# Comm.net
KiCad netlist of a schematic drawn in Altium Designer
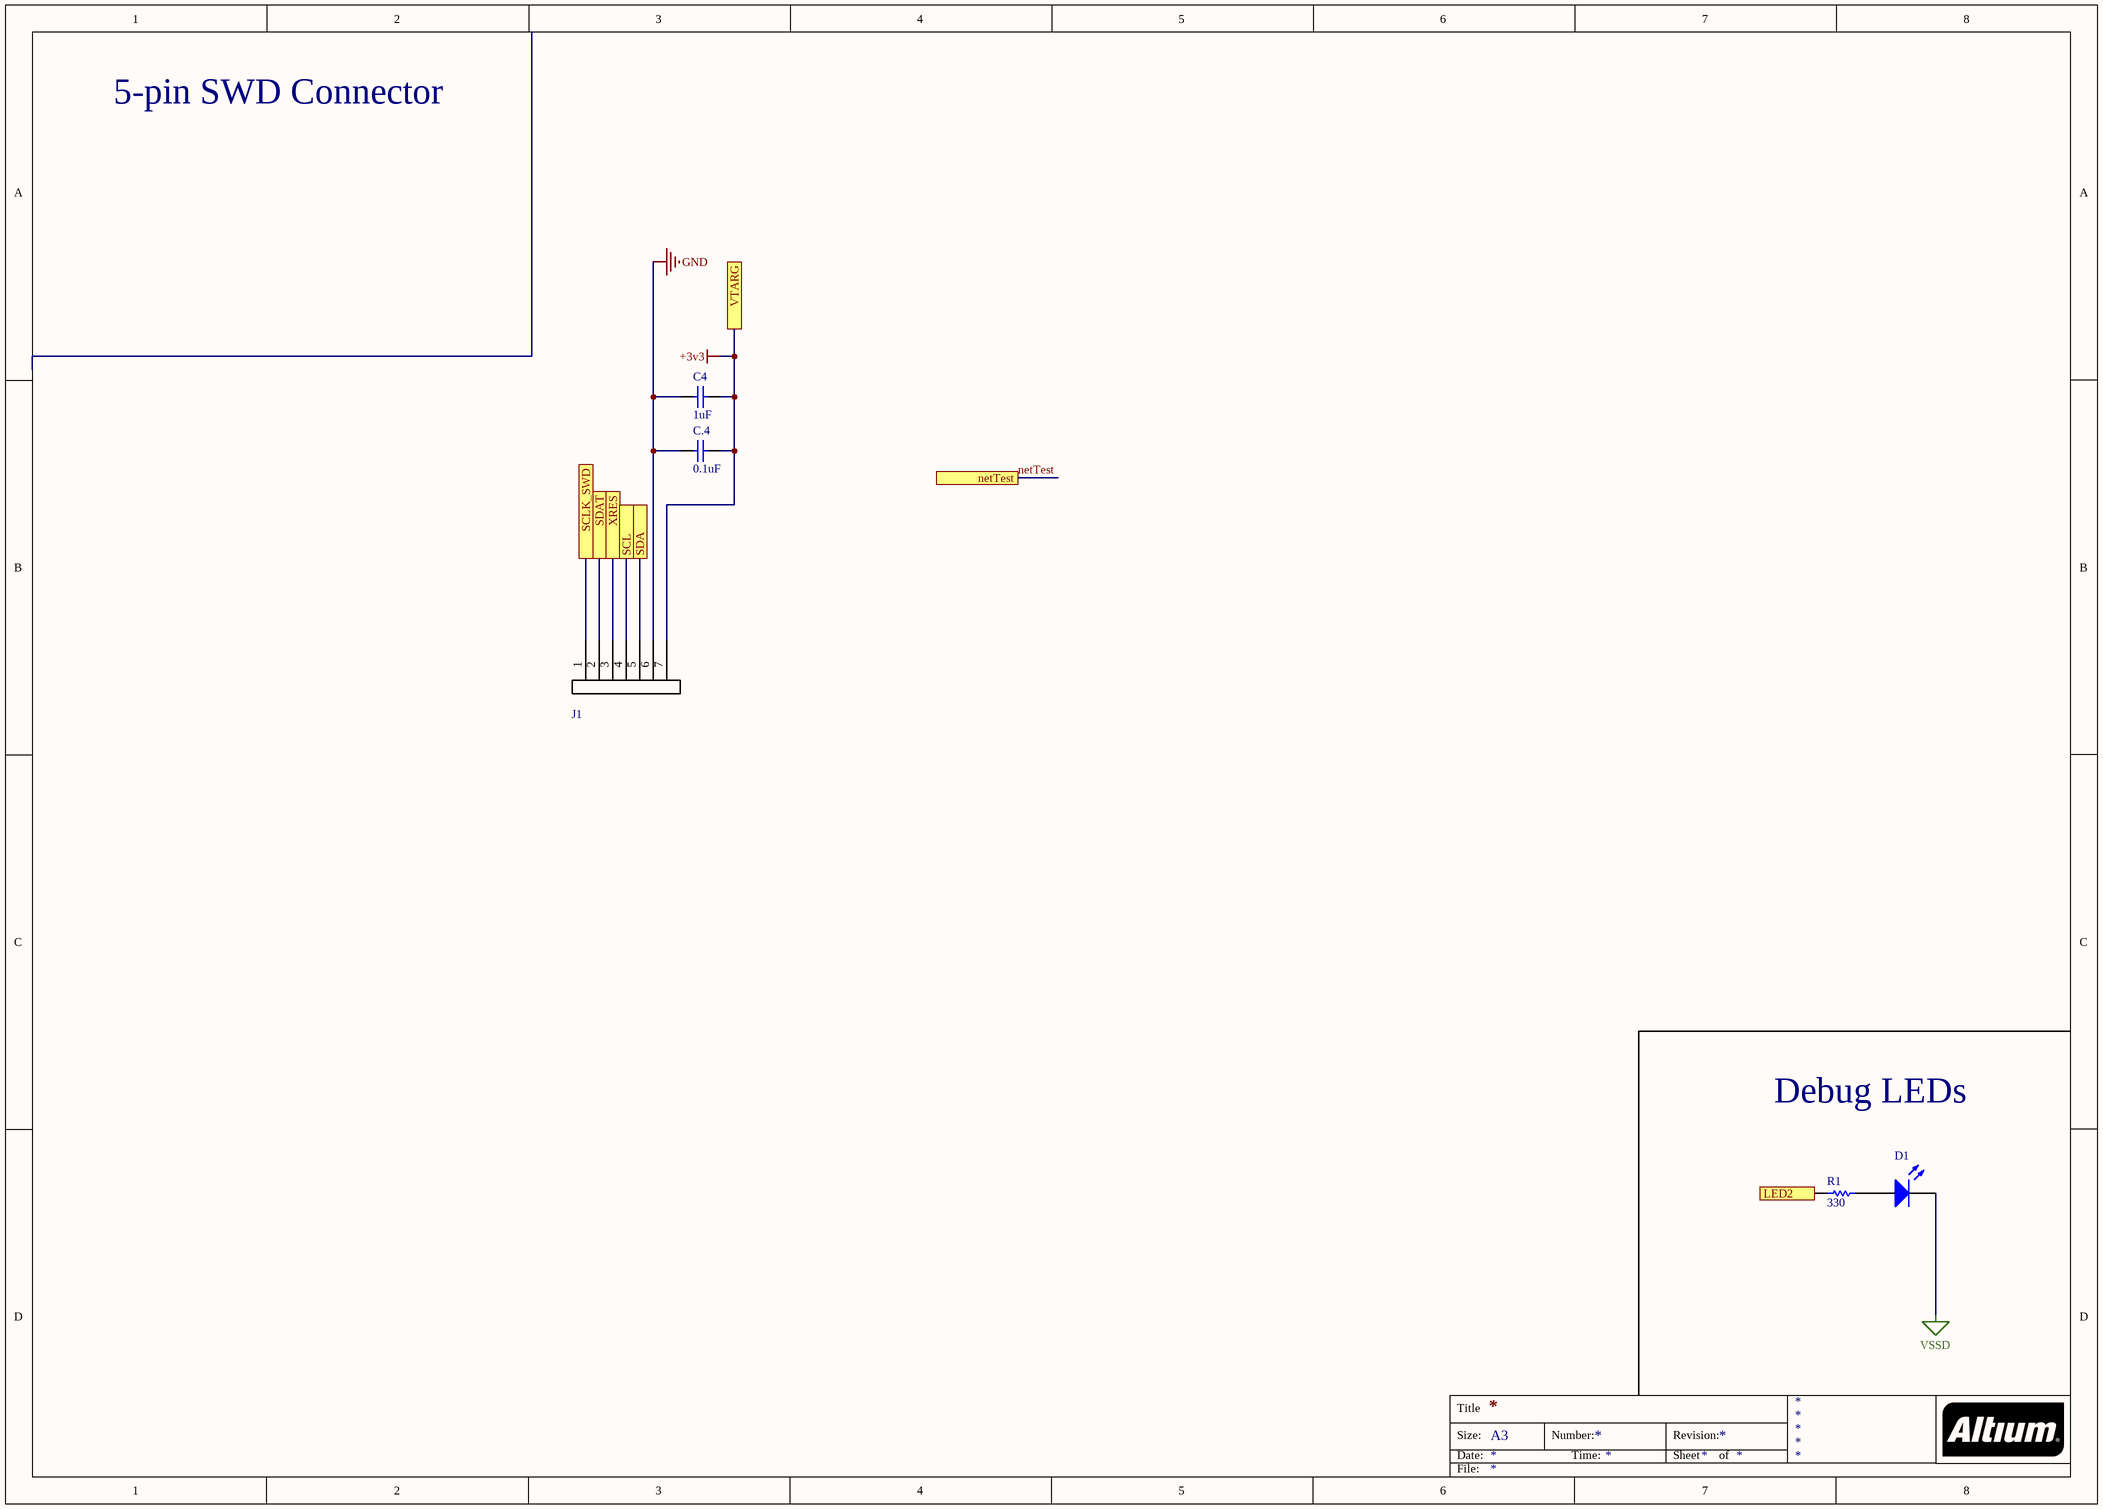
[diagram p0: Comm.SchDoc]

(export (version "E")
  (design (tool "Eeschema 10.0.6"))
  (components
    (comp (ref "C.4")
      (value "0.1uF")
      (footprint "CAPC0603(1608)100_N")
      (description "CAP 0.1 uF 50V ±20% 0603 (1608 Metric) Thickness 1mm SMD")
      (fields (field (name "TOLERANCE") "Â±20%"))
      (libsource (lib "Altium Content Vault") (part "CAP"))
    )
    (comp (ref "C4")
      (value "1uF")
      (footprint "CAPC0603(1608)100_N")
      (description "CAP 1uF 50V ±20% 0603 (1608 Metric) Thickness 1mm SMD")
      (fields (field (name "TOLERANCE") "Â±20%"))
      (libsource (lib "Altium Content Vault") (part "CAP"))
    )
    (comp (ref "D1")
      (value "150060BS75000")
      (footprint "0603_A")
      (description "SMD mono-color Chip LED, WL-SMCW, Blue")
      (fields (field (name "MANUFACTURER") "Wuerth Elektronik"))
      (libsource (lib "Altium Content Vault") (part "WE-LED_K1A2-2"))
    )
    (comp (ref "J1")
      (value "BM07B-NSHSS-TBT (LF)(SN)")
      (footprint "BM07B-NSHSS-TBT (LF)(SN)")
      (libsource (lib "Pads") (part "BM07B-NSHSS-TBT (LF)(SN)"))
    )
    (comp (ref "R1")
      (value "330")
      (footprint "RESC0603(1608)_L")
      (description "330R 0.1W 5% 0603 (1608 Metric)  SMD")
      (fields (field (name "TOLERANCE") "5 %") (field (name "POWER") "0.1 W"))
      (libsource (lib "Altium Content Vault") (part "RES"))
    )
  )
  (nets
    (net (code "1") (name "+3v3") (class "Default")
      (node (ref "C.4") (pin "1") (pinfunction "1_1") (pintype "passive"))
      (node (ref "C4") (pin "1") (pinfunction "1_1") (pintype "passive"))
      (node (ref "J1") (pin "7") (pinfunction "0_7") (pintype "passive"))
    )
    (net (code "2") (name "/LED2") (class "Default")
      (node (ref "R1") (pin "1") (pinfunction "1_1") (pintype "passive"))
    )
    (net (code "3") (name "/SCL") (class "Default")
      (node (ref "J1") (pin "4") (pinfunction "0_4") (pintype "passive"))
    )
    (net (code "4") (name "/SCLK_SWD") (class "Default")
      (node (ref "J1") (pin "1") (pinfunction "0_1") (pintype "passive"))
    )
    (net (code "5") (name "/SDA") (class "Default")
      (node (ref "J1") (pin "5") (pinfunction "0_5") (pintype "passive"))
    )
    (net (code "6") (name "/SDAT") (class "Default")
      (node (ref "J1") (pin "2") (pinfunction "0_2") (pintype "passive"))
    )
    (net (code "7") (name "/XRES") (class "Default")
      (node (ref "J1") (pin "3") (pinfunction "0_3") (pintype "passive"))
    )
    (net (code "9") (name "GND") (class "Default")
      (node (ref "C.4") (pin "2") (pinfunction "2_2") (pintype "passive"))
      (node (ref "C4") (pin "2") (pinfunction "2_2") (pintype "passive"))
      (node (ref "J1") (pin "6") (pinfunction "0_6") (pintype "passive"))
    )
    (net (code "10") (name "Net-(D1-A)") (class "Default")
      (node (ref "D1") (pin "2") (pinfunction "A_2") (pintype "passive"))
      (node (ref "R1") (pin "2") (pinfunction "2_2") (pintype "passive"))
    )
    (net (code "11") (name "VSSD") (class "Default")
      (node (ref "D1") (pin "1") (pinfunction "K_1") (pintype "passive"))
    )
  )
)
